# VoltageRegulator5V.net
KiCad netlist of a schematic drawn in Altium Designer
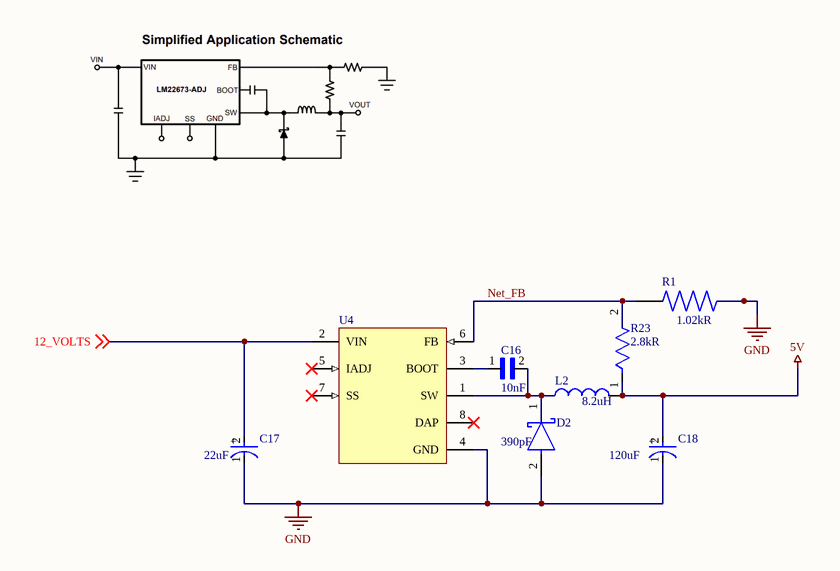
[diagram p0: VoltageRegulator5V.SchDoc]

(export (version "E")
  (design (tool "Eeschema 10.0.6"))
  (components
    (comp (ref "C16")
      (value "10nF")
      (footprint "CAPC2012X100N")
      (description "CAP CER 0805 10NF 50V C0G 1%")
      (fields (field (name "MP") "C0805C103F5GECAUTO") (field (name "MANUFACTURER") "KEMET"))
      (libsource (lib "C0805C103F5GECAUTO") (part "C0805C103F5GECAUTO"))
    )
    (comp (ref "C17")
      (value "22uF")
      (footprint "FP-OS-CON-SMT-C6-MFG")
      (description "Conductive Polymer Aluminum Solid Capacitors (OS-CON) 22uF ±20% 35V")
      (fields (field (name "MANUFACTURER") "Panasonic") (field (name "MANUFACTURER PART NUMBER") "35SVF22M"))
      (libsource (lib "Altium Content Vault") (part "a00bbbee19879c290e62620ae7e47b1"))
    )
    (comp (ref "C18")
      (value "16SVPC120M")
      (footprint "FP-OS-CON-SMT-E7-MFG")
      (description "Conductive Polymer Aluminum Solid Capacitors (OS-CON) 120uF ±20% 16V RADIAL SMT 8x6.9mm")
      (fields
        (field (name "CAPACITANCE") "120uF")
        (field (name "VOLTAGE") "16V")
        (field (name "TOLERANCE") "20%")
      )
      (libsource (lib "Altium Content Vault") (part "cf48714ba7e38822c1575c7ec0b6d1f"))
    )
    (comp (ref "D2")
      (value "390pF")
      (footprint "FP-95401-MFG")
      (description "DIODE SCHOTTKY 15V 1A DO214AA")
      (fields
        (field (name "MANUFACTURER PART NUMBER") "VS-10BQ015-M3/5BT")
        (field (name "OCTOPART") "https://octopart.com/vs-10bq015-m3%2F5bt-vishay-39003459")
      )
      (libsource (lib "Altium Content Vault") (part "1d6ec82d83fb6aee721767c19dac4b9"))
    )
    (comp (ref "L2")
      (value "8.2uH")
      (footprint "INDC2012X145N")
      (description "Ind Chip Shielded Multi-Layer 8.2uH 10% 4MHz 45Q-Factor Ferrite 15mA 0805 T/R")
      (fields (field (name "MP") "CV201210-8R2K") (field (name "MANUFACTURER") "Bourns"))
      (libsource (lib "CV201210-8R2K") (part "CV201210-8R2K"))
    )
    (comp (ref "R1")
      (value "ERJ-PB6B1021V")
      (footprint "RESC2012X70N")
      (description "Res SMD 1.02K Ohm 0.1% 1/4W 0805")
      (fields
        (field (name "MANUFACTURER") "Panasonic")
        (field (name "RESISTANCE") "1.02kR")
        (field (name "TOLERANCE") "0.1%")
      )
      (libsource (lib "ERJ-PB6B1021V") (part "ERJ-PB6B1021V"))
    )
    (comp (ref "R23")
      (value "RNCP0805FTD2K80")
      (footprint "FP-RNCP0805-MFG")
      (description "2.8kΩ ±1% 0.25W 0805 High Power Anti-Sulfur Thin Film Chip Resistor")
      (fields
        (field (name "TOLERANCE") "1%")
        (field (name "RESISTANCE") "2.8kR")
        (field (name "MANUFACTURER") "Stackpole Electronics")
      )
      (libsource (lib "Altium Content Vault") (part "1029c3af85768c4190bb7ad29bc67b5"))
    )
    (comp (ref "U4")
      (value "LM22673TJE-5.0/NOPB")
      (footprint "TJ7A_M")
      (fields (field (name "MANUFACTURER") "National Semiconductor"))
      (libsource (lib "Altium Content Vault") (part "PM-REG-LM22673TJ"))
    )
  )
  (nets
    (net (code "1") (name "/Net_FB") (class "Default")
      (node (ref "R1") (pin "1") (pinfunction "1_1") (pintype "passive"))
      (node (ref "R23") (pin "2") (pinfunction "2_2") (pintype "passive"))
      (node (ref "U4") (pin "6") (pinfunction "FB_6") (pintype "input"))
    )
    (net (code "2") (name "5V") (class "Default")
      (node (ref "C18") (pin "2") (pinfunction "A_2") (pintype "passive"))
      (node (ref "L2") (pin "2") (pinfunction "2_2") (pintype "passive"))
      (node (ref "R23") (pin "1") (pinfunction "1_1") (pintype "passive"))
    )
    (net (code "3") (name "12_VOLTS") (class "Default")
      (node (ref "C17") (pin "2") (pinfunction "A_2") (pintype "passive"))
      (node (ref "U4") (pin "2") (pinfunction "VIN_2") (pintype "power_in"))
    )
    (net (code "4") (name "GND") (class "Default")
      (node (ref "C17") (pin "1") (pinfunction "C_1") (pintype "passive"))
      (node (ref "C18") (pin "1") (pinfunction "C_1") (pintype "passive"))
      (node (ref "D2") (pin "2") (pinfunction "A_2") (pintype "passive"))
      (node (ref "R1") (pin "2") (pinfunction "2_2") (pintype "passive"))
      (node (ref "U4") (pin "4") (pinfunction "GND_4") (pintype "power_in"))
    )
    (net (code "5") (name "Net-(D2-C)") (class "Default")
      (node (ref "C16") (pin "2") (pinfunction "2_2") (pintype "passive"))
      (node (ref "D2") (pin "1") (pinfunction "C_1") (pintype "passive"))
      (node (ref "L2") (pin "1") (pinfunction "1_1") (pintype "passive"))
      (node (ref "U4") (pin "1") (pinfunction "SW_1") (pintype "power_in"))
    )
    (net (code "6") (name "Net-(U4-BOOT)") (class "Default")
      (node (ref "C16") (pin "1") (pinfunction "1_1") (pintype "passive"))
      (node (ref "U4") (pin "3") (pinfunction "BOOT_3") (pintype "passive"))
    )
    (net (code "7") (name "unconnected-(U4-DAP-Pad8)") (class "Default")
      (node (ref "U4") (pin "8") (pinfunction "DAP_8") (pintype "power_in+no_connect"))
    )
    (net (code "8") (name "unconnected-(U4-IADJ-Pad5)") (class "Default")
      (node (ref "U4") (pin "5") (pinfunction "IADJ_5") (pintype "input+no_connect"))
    )
    (net (code "9") (name "unconnected-(U4-SS-Pad7)") (class "Default")
      (node (ref "U4") (pin "7") (pinfunction "SS_7") (pintype "input+no_connect"))
    )
  )
)
